# Column.net
KiCad netlist of a schematic drawn in Altium Designer
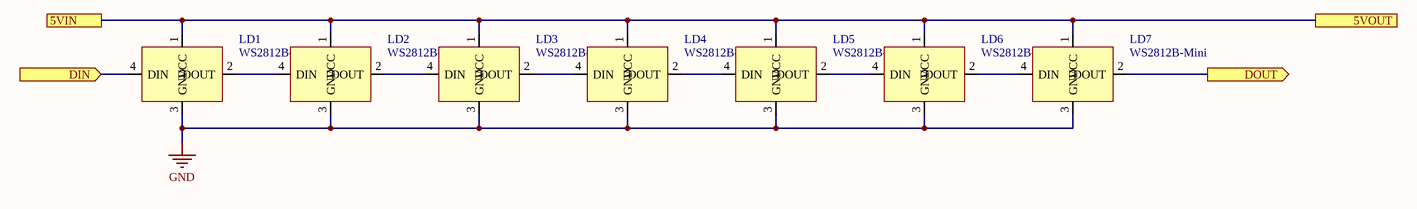
[diagram p0: Column.SchDoc]

(export (version "E")
  (design (tool "Eeschema 10.0.6"))
  (components
    (comp (ref "LD1")
      (value "WS2812B-Mini")
      (footprint "WS2812B-Mini")
      (description "C114583")
      (libsource (lib "rgbleds") (part "WS2812"))
    )
    (comp (ref "LD2")
      (value "WS2812B-Mini")
      (footprint "WS2812B-Mini")
      (description "C114583")
      (libsource (lib "rgbleds") (part "WS2812"))
    )
    (comp (ref "LD3")
      (value "WS2812B-Mini")
      (footprint "WS2812B-Mini")
      (description "C114583")
      (libsource (lib "rgbleds") (part "WS2812"))
    )
    (comp (ref "LD4")
      (value "WS2812B-Mini")
      (footprint "WS2812B-Mini")
      (description "C114583")
      (libsource (lib "rgbleds") (part "WS2812"))
    )
    (comp (ref "LD5")
      (value "WS2812B-Mini")
      (footprint "WS2812B-Mini")
      (description "C114583")
      (libsource (lib "rgbleds") (part "WS2812"))
    )
    (comp (ref "LD6")
      (value "WS2812B-Mini")
      (footprint "WS2812B-Mini")
      (description "C114583")
      (libsource (lib "rgbleds") (part "WS2812"))
    )
    (comp (ref "LD7")
      (value "WS2812B-Mini")
      (footprint "WS2812B-Mini")
      (description "C114583")
      (libsource (lib "rgbleds") (part "WS2812"))
    )
  )
  (nets
    (net (code "1") (name "/5VIN") (class "Default")
      (node (ref "LD1") (pin "1") (pinfunction "VCC_1") (pintype "passive"))
      (node (ref "LD2") (pin "1") (pinfunction "VCC_1") (pintype "passive"))
      (node (ref "LD3") (pin "1") (pinfunction "VCC_1") (pintype "passive"))
      (node (ref "LD4") (pin "1") (pinfunction "VCC_1") (pintype "passive"))
      (node (ref "LD5") (pin "1") (pinfunction "VCC_1") (pintype "passive"))
      (node (ref "LD6") (pin "1") (pinfunction "VCC_1") (pintype "passive"))
      (node (ref "LD7") (pin "1") (pinfunction "VCC_1") (pintype "passive"))
    )
    (net (code "2") (name "/DIN") (class "Default")
      (node (ref "LD1") (pin "4") (pinfunction "DIN_4") (pintype "passive"))
    )
    (net (code "3") (name "/DOUT") (class "Default")
      (node (ref "LD7") (pin "2") (pinfunction "DOUT_2") (pintype "passive"))
    )
    (net (code "4") (name "GND") (class "Default")
      (node (ref "LD1") (pin "3") (pinfunction "GND_3") (pintype "passive"))
      (node (ref "LD2") (pin "3") (pinfunction "GND_3") (pintype "passive"))
      (node (ref "LD3") (pin "3") (pinfunction "GND_3") (pintype "passive"))
      (node (ref "LD4") (pin "3") (pinfunction "GND_3") (pintype "passive"))
      (node (ref "LD5") (pin "3") (pinfunction "GND_3") (pintype "passive"))
      (node (ref "LD6") (pin "3") (pinfunction "GND_3") (pintype "passive"))
      (node (ref "LD7") (pin "3") (pinfunction "GND_3") (pintype "passive"))
    )
    (net (code "5") (name "Net-(LD1-DOUT)") (class "Default")
      (node (ref "LD1") (pin "2") (pinfunction "DOUT_2") (pintype "passive"))
      (node (ref "LD2") (pin "4") (pinfunction "DIN_4") (pintype "passive"))
    )
    (net (code "6") (name "Net-(LD2-DOUT)") (class "Default")
      (node (ref "LD2") (pin "2") (pinfunction "DOUT_2") (pintype "passive"))
      (node (ref "LD3") (pin "4") (pinfunction "DIN_4") (pintype "passive"))
    )
    (net (code "7") (name "Net-(LD3-DOUT)") (class "Default")
      (node (ref "LD3") (pin "2") (pinfunction "DOUT_2") (pintype "passive"))
      (node (ref "LD4") (pin "4") (pinfunction "DIN_4") (pintype "passive"))
    )
    (net (code "8") (name "Net-(LD4-DOUT)") (class "Default")
      (node (ref "LD4") (pin "2") (pinfunction "DOUT_2") (pintype "passive"))
      (node (ref "LD5") (pin "4") (pinfunction "DIN_4") (pintype "passive"))
    )
    (net (code "9") (name "Net-(LD5-DOUT)") (class "Default")
      (node (ref "LD5") (pin "2") (pinfunction "DOUT_2") (pintype "passive"))
      (node (ref "LD6") (pin "4") (pinfunction "DIN_4") (pintype "passive"))
    )
    (net (code "10") (name "Net-(LD6-DOUT)") (class "Default")
      (node (ref "LD6") (pin "2") (pinfunction "DOUT_2") (pintype "passive"))
      (node (ref "LD7") (pin "4") (pinfunction "DIN_4") (pintype "passive"))
    )
  )
)
